# OPEN_DROP_DIGISCOPE.net
KiCad netlist of a schematic drawn in EAGLE
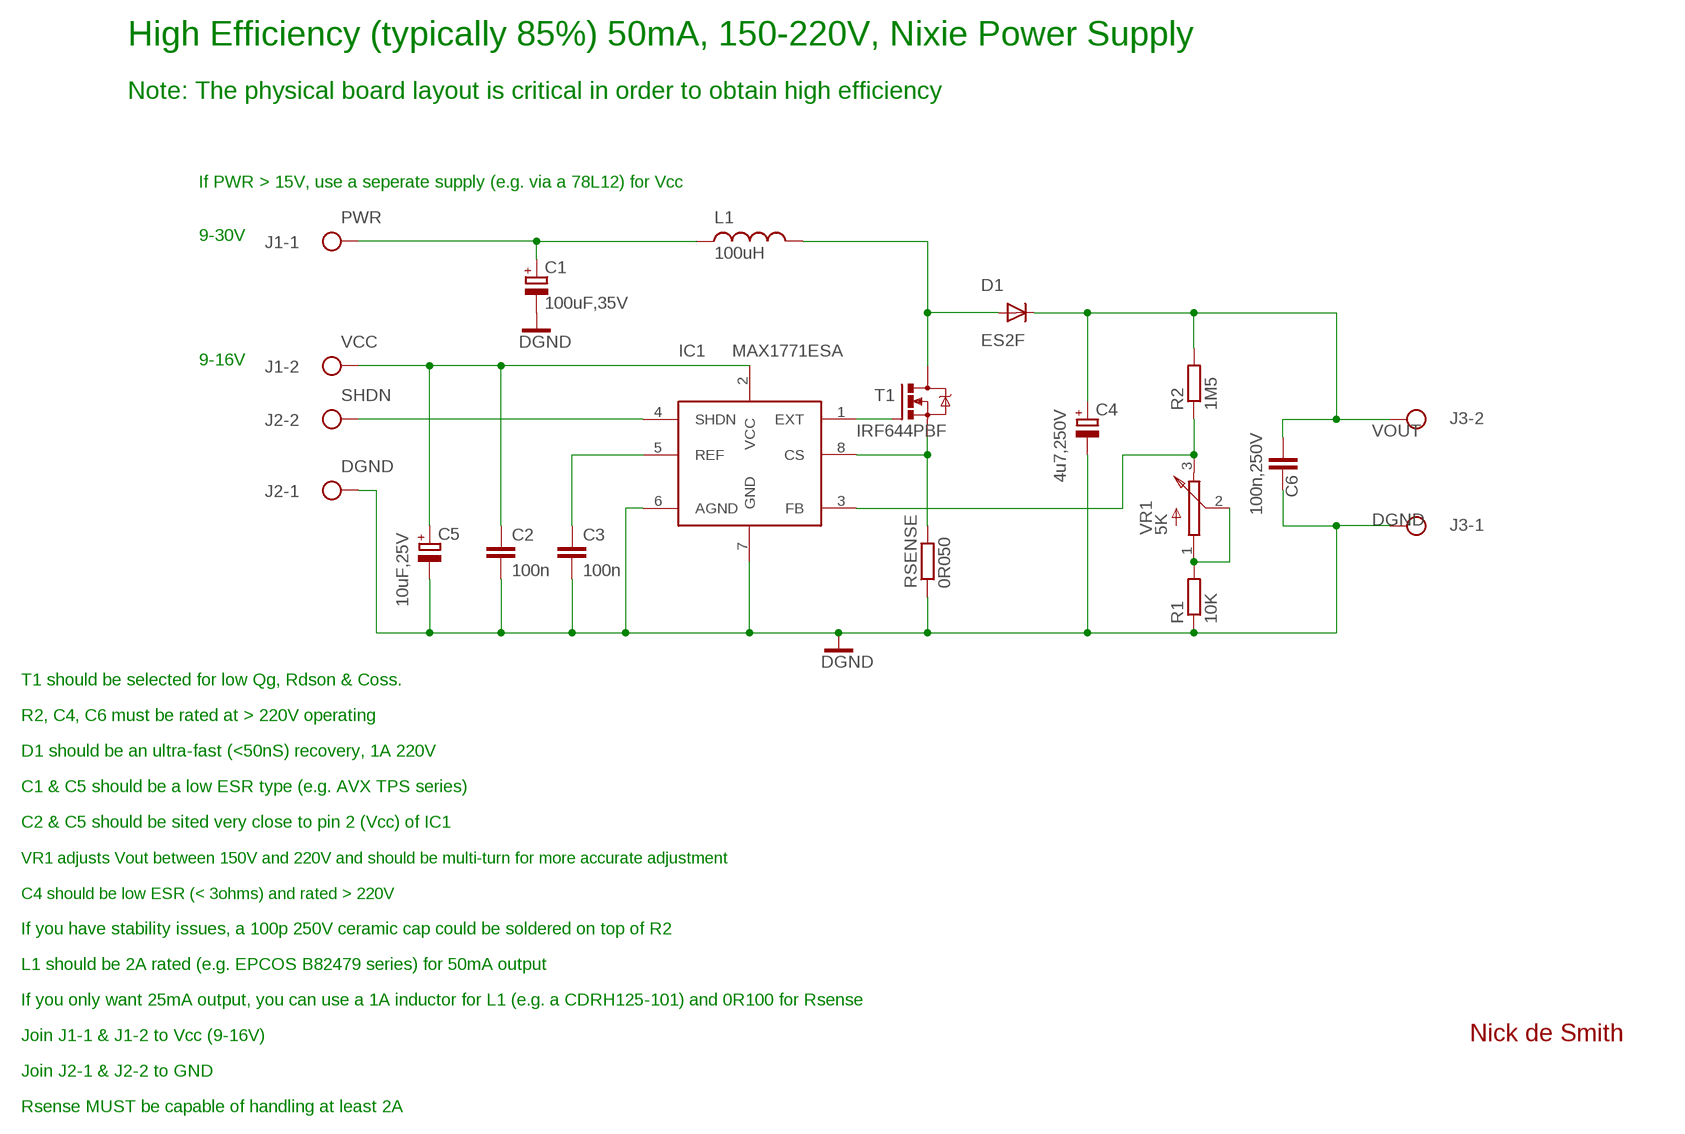
[diagram p0: schematic, sheet 1]

(export (version "E")
  (design (tool "Eeschema 10.0.6"))
  (components
    (comp (ref "C1")
      (value "100uF,35V")
      (footprint "eagle-import:C-EIA-7343")
      (libsource (lib "eagle-import") (part "C-POL-EU7343"))
    )
    (comp (ref "C2")
      (value "100n")
      (footprint "eagle-import:C0805")
      (libsource (lib "eagle-import") (part "C-EUC0805"))
    )
    (comp (ref "C3")
      (value "100n")
      (footprint "eagle-import:C0805")
      (libsource (lib "eagle-import") (part "C-EUC0805"))
    )
    (comp (ref "C4")
      (value "4u7,250V")
      (footprint "eagle-import:NICHICON-UJ-12")
      (libsource (lib "eagle-import") (part "C-POL-EU-NICHICON-UJ-12"))
    )
    (comp (ref "C5")
      (value "10uF,25V")
      (footprint "eagle-import:C-EIA-7343")
      (libsource (lib "eagle-import") (part "C-POL-EU7343"))
    )
    (comp (ref "C6")
      (value "100n,250V")
      (footprint "eagle-import:C2420")
      (libsource (lib "eagle-import") (part "C-EU-2420"))
    )
    (comp (ref "D1")
      (value "ES2F")
      (footprint "eagle-import:SMC")
      (libsource (lib "eagle-import") (part "DIODE-SMC"))
    )
    (comp (ref "IC1")
      (value "MAX1771ESA")
      (footprint "eagle-import:SO-8")
      (libsource (lib "eagle-import") (part "MAX1771ESA"))
    )
    (comp (ref "J1")
      (value "TERM-BLOCK-2-02IN")
      (footprint "eagle-import:SCREW-2-02")
      (libsource (lib "eagle-import") (part "TERM-BLOCK-2-02IN"))
    )
    (comp (ref "J2")
      (value "TERM-BLOCK-2-02IN")
      (footprint "eagle-import:SCREW-2-02")
      (libsource (lib "eagle-import") (part "TERM-BLOCK-2-02IN"))
    )
    (comp (ref "J3")
      (value "TERM-BLOCK-2-02IN")
      (footprint "eagle-import:SCREW-2-02")
      (libsource (lib "eagle-import") (part "TERM-BLOCK-2-02IN"))
    )
    (comp (ref "L1")
      (value "100uH")
      (footprint "eagle-import:L-B82479")
      (libsource (lib "eagle-import") (part "L-SMT-POWER-B82479"))
    )
    (comp (ref "R1")
      (value "10K")
      (footprint "eagle-import:R0805")
      (libsource (lib "eagle-import") (part "R-EU_R0805"))
    )
    (comp (ref "R2")
      (value "1M5")
      (footprint "eagle-import:R2512")
      (libsource (lib "eagle-import") (part "R-EU_R2512"))
    )
    (comp (ref "RSENSE")
      (value "0R050")
      (footprint "eagle-import:R2010")
      (libsource (lib "eagle-import") (part "R-EU_R2010"))
    )
    (comp (ref "T1")
      (value "IRF644PBF")
      (footprint "eagle-import:TO220BV")
      (libsource (lib "eagle-import") (part "IRF740"))
    )
    (comp (ref "VR1")
      (value "5K")
      (footprint "eagle-import:BOURNS-3214W")
      (libsource (lib "eagle-import") (part "TRIMPOT-3214W"))
    )
  )
  (nets
    (net (code "1") (name "/PWR") (class "Default")
      (node (ref "C1") (pin "+") (pinfunction "+_+") (pintype "passive"))
      (node (ref "J1") (pin "1") (pinfunction "P$1_1") (pintype "passive"))
      (node (ref "L1") (pin "P$1") (pinfunction "1_P$1") (pintype "passive"))
    )
    (net (code "2") (name "/SHDN") (class "Default")
      (node (ref "IC1") (pin "4") (pinfunction "SHDN_4") (pintype "input"))
      (node (ref "J2") (pin "2") (pinfunction "P$1_2") (pintype "passive"))
    )
    (net (code "3") (name "/VCC") (class "Default")
      (node (ref "C2") (pin "1") (pinfunction "1_1") (pintype "passive"))
      (node (ref "C5") (pin "+") (pinfunction "+_+") (pintype "passive"))
      (node (ref "IC1") (pin "2") (pinfunction "VCC_2") (pintype "input"))
      (node (ref "J1") (pin "2") (pinfunction "P$1_2") (pintype "passive"))
    )
    (net (code "4") (name "/VOUT") (class "Default")
      (node (ref "C4") (pin "2") (pinfunction "+_2") (pintype "passive"))
      (node (ref "C6") (pin "P$1") (pinfunction "1_P$1") (pintype "passive"))
      (node (ref "D1") (pin "C") (pinfunction "C_C") (pintype "passive"))
      (node (ref "J3") (pin "2") (pinfunction "P$1_2") (pintype "passive"))
      (node (ref "R2") (pin "2") (pinfunction "2_2") (pintype "passive"))
    )
    (net (code "5") (name "DGND") (class "Default")
      (node (ref "C1") (pin "-") (pinfunction "-_-") (pintype "passive"))
      (node (ref "C2") (pin "2") (pinfunction "2_2") (pintype "passive"))
      (node (ref "C3") (pin "2") (pinfunction "2_2") (pintype "passive"))
      (node (ref "C4") (pin "1") (pinfunction "-_1") (pintype "passive"))
      (node (ref "C5") (pin "-") (pinfunction "-_-") (pintype "passive"))
      (node (ref "C6") (pin "P$2") (pinfunction "2_P$2") (pintype "passive"))
      (node (ref "IC1") (pin "6") (pinfunction "AGND_6") (pintype "input"))
      (node (ref "IC1") (pin "7") (pinfunction "GND_7") (pintype "input"))
      (node (ref "J2") (pin "1") (pinfunction "P$1_1") (pintype "passive"))
      (node (ref "J3") (pin "1") (pinfunction "P$1_1") (pintype "passive"))
      (node (ref "R1") (pin "1") (pinfunction "1_1") (pintype "passive"))
      (node (ref "RSENSE") (pin "1") (pinfunction "1_1") (pintype "passive"))
    )
    (net (code "6") (name "Net-(IC1-CS)") (class "Default")
      (node (ref "IC1") (pin "8") (pinfunction "CS_8") (pintype "input"))
      (node (ref "RSENSE") (pin "2") (pinfunction "2_2") (pintype "passive"))
      (node (ref "T1") (pin "S") (pinfunction "S_S") (pintype "passive"))
    )
    (net (code "7") (name "Net-(IC1-EXT)") (class "Default")
      (node (ref "IC1") (pin "1") (pinfunction "EXT_1") (pintype "output"))
      (node (ref "T1") (pin "G") (pinfunction "G_G") (pintype "passive"))
    )
    (net (code "8") (name "Net-(IC1-FB)") (class "Default")
      (node (ref "IC1") (pin "3") (pinfunction "FB_3") (pintype "input"))
      (node (ref "R2") (pin "1") (pinfunction "1_1") (pintype "passive"))
      (node (ref "VR1") (pin "3") (pinfunction "B_3") (pintype "passive"))
    )
    (net (code "9") (name "Net-(IC1-REF)") (class "Default")
      (node (ref "C3") (pin "1") (pinfunction "1_1") (pintype "passive"))
      (node (ref "IC1") (pin "5") (pinfunction "REF_5") (pintype "input"))
    )
    (net (code "10") (name "Net-(L1-2)") (class "Default")
      (node (ref "D1") (pin "A") (pinfunction "A_A") (pintype "passive"))
      (node (ref "L1") (pin "P$2") (pinfunction "2_P$2") (pintype "passive"))
      (node (ref "T1") (pin "D") (pinfunction "D_D") (pintype "passive"))
    )
    (net (code "11") (name "Net-(VR1-A)") (class "Default")
      (node (ref "R1") (pin "2") (pinfunction "2_2") (pintype "passive"))
      (node (ref "VR1") (pin "1") (pinfunction "A_1") (pintype "passive"))
      (node (ref "VR1") (pin "2") (pinfunction "W_2") (pintype "passive"))
    )
  )
)
